# UPCB.net
KiCad netlist of a schematic drawn in EAGLE
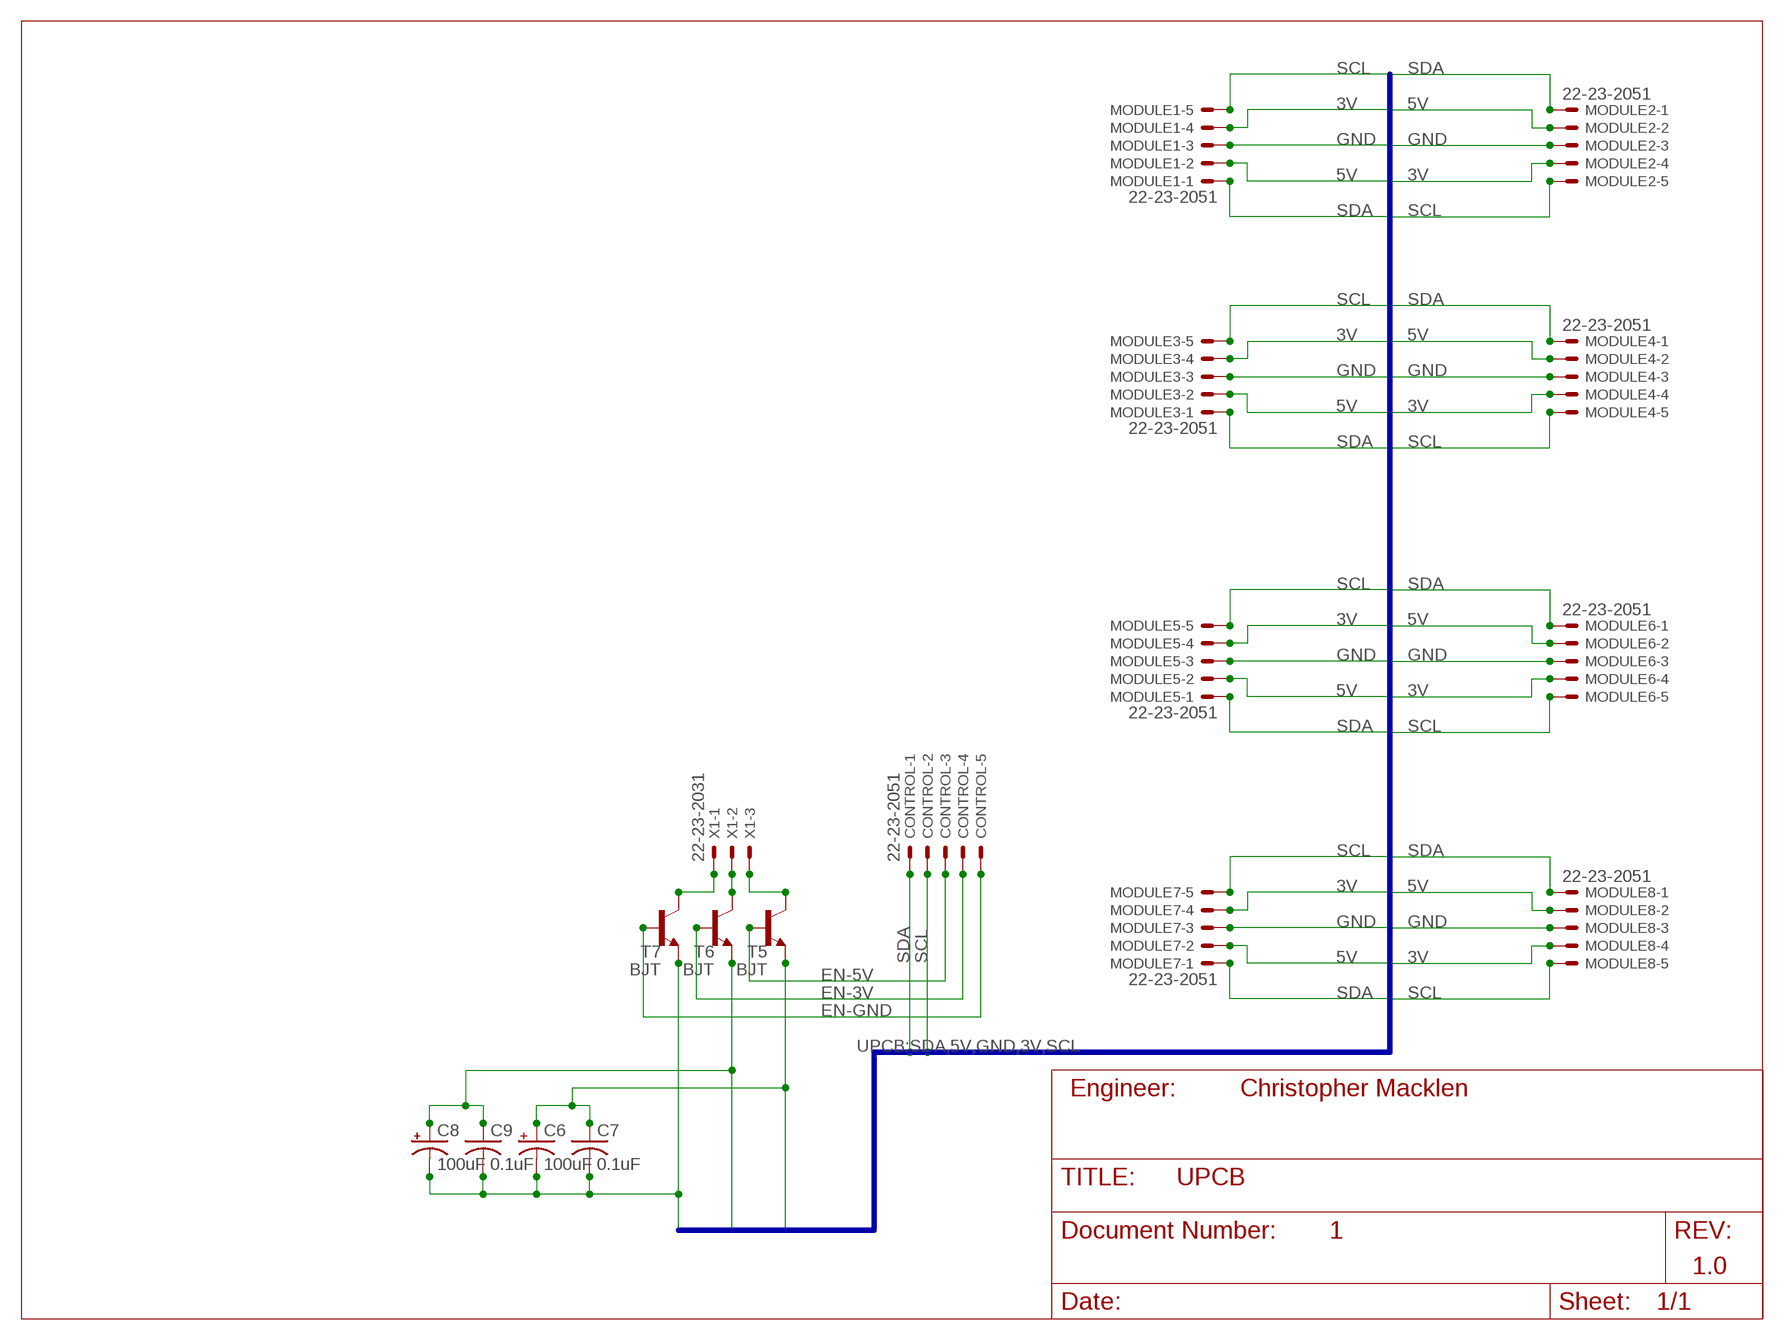
[diagram p0: schematic, sheet 1]

(export (version "E")
  (design (tool "Eeschema 10.0.6"))
  (components
    (comp (ref "C6")
      (value "100uF")
      (footprint "eagle-import:E2-5")
      (libsource (lib "eagle-import") (part "CPOL-USE2-5"))
    )
    (comp (ref "C7")
      (value "0.1uF")
      (footprint "eagle-import:C025-024X044")
      (libsource (lib "eagle-import") (part "C-US025-024X044"))
    )
    (comp (ref "C8")
      (value "100uF")
      (footprint "eagle-import:E2-5")
      (libsource (lib "eagle-import") (part "CPOL-USE2-5"))
    )
    (comp (ref "C9")
      (value "0.1uF")
      (footprint "eagle-import:C025-024X044")
      (libsource (lib "eagle-import") (part "C-US025-024X044"))
    )
    (comp (ref "CONTROL")
      (value "22-23-2051")
      (footprint "eagle-import:22-23-2051")
      (fields (field (name "MF") "MOLEX"))
      (libsource (lib "eagle-import") (part "22-23-2051"))
    )
    (comp (ref "MODULE1")
      (value "22-23-2051")
      (footprint "eagle-import:22-23-2051")
      (fields (field (name "MF") "MOLEX"))
      (libsource (lib "eagle-import") (part "22-23-2051"))
    )
    (comp (ref "MODULE2")
      (value "22-23-2051")
      (footprint "eagle-import:22-23-2051")
      (fields (field (name "MF") "MOLEX"))
      (libsource (lib "eagle-import") (part "22-23-2051"))
    )
    (comp (ref "MODULE3")
      (value "22-23-2051")
      (footprint "eagle-import:22-23-2051")
      (fields (field (name "MF") "MOLEX"))
      (libsource (lib "eagle-import") (part "22-23-2051"))
    )
    (comp (ref "MODULE4")
      (value "22-23-2051")
      (footprint "eagle-import:22-23-2051")
      (fields (field (name "MF") "MOLEX"))
      (libsource (lib "eagle-import") (part "22-23-2051"))
    )
    (comp (ref "MODULE5")
      (value "22-23-2051")
      (footprint "eagle-import:22-23-2051")
      (fields (field (name "MF") "MOLEX"))
      (libsource (lib "eagle-import") (part "22-23-2051"))
    )
    (comp (ref "MODULE6")
      (value "22-23-2051")
      (footprint "eagle-import:22-23-2051")
      (fields (field (name "MF") "MOLEX"))
      (libsource (lib "eagle-import") (part "22-23-2051"))
    )
    (comp (ref "MODULE7")
      (value "22-23-2051")
      (footprint "eagle-import:22-23-2051")
      (fields (field (name "MF") "MOLEX"))
      (libsource (lib "eagle-import") (part "22-23-2051"))
    )
    (comp (ref "MODULE8")
      (value "22-23-2051")
      (footprint "eagle-import:22-23-2051")
      (fields (field (name "MF") "MOLEX"))
      (libsource (lib "eagle-import") (part "22-23-2051"))
    )
    (comp (ref "T5")
      (value "BJT")
      (footprint "eagle-import:TO92-E1")
      (libsource (lib "eagle-import") (part "-NPN-TO92-E1"))
    )
    (comp (ref "T6")
      (value "BJT")
      (footprint "eagle-import:TO92-E1")
      (libsource (lib "eagle-import") (part "-NPN-TO92-E1"))
    )
    (comp (ref "T7")
      (value "BJT")
      (footprint "eagle-import:TO92-E1")
      (libsource (lib "eagle-import") (part "-NPN-TO92-E1"))
    )
    (comp (ref "X1")
      (value "22-23-2031")
      (footprint "eagle-import:22-23-2031")
      (fields (field (name "MF") "MOLEX"))
      (libsource (lib "eagle-import") (part "22-23-2031"))
    )
  )
  (nets
    (net (code "2") (name "/3V") (class "Default")
      (node (ref "C8") (pin "+") (pinfunction "+_+") (pintype "passive"))
      (node (ref "C9") (pin "1") (pinfunction "1_1") (pintype "passive"))
      (node (ref "MODULE1") (pin "4") (pinfunction "S_4") (pintype "passive"))
      (node (ref "MODULE2") (pin "4") (pinfunction "S_4") (pintype "passive"))
      (node (ref "MODULE3") (pin "4") (pinfunction "S_4") (pintype "passive"))
      (node (ref "MODULE4") (pin "4") (pinfunction "S_4") (pintype "passive"))
      (node (ref "MODULE5") (pin "4") (pinfunction "S_4") (pintype "passive"))
      (node (ref "MODULE6") (pin "4") (pinfunction "S_4") (pintype "passive"))
      (node (ref "MODULE7") (pin "4") (pinfunction "S_4") (pintype "passive"))
      (node (ref "MODULE8") (pin "4") (pinfunction "S_4") (pintype "passive"))
      (node (ref "T6") (pin "3") (pinfunction "E_3") (pintype "passive"))
    )
    (net (code "3") (name "/5V") (class "Default")
      (node (ref "C6") (pin "+") (pinfunction "+_+") (pintype "passive"))
      (node (ref "C7") (pin "1") (pinfunction "1_1") (pintype "passive"))
      (node (ref "MODULE1") (pin "2") (pinfunction "S_2") (pintype "passive"))
      (node (ref "MODULE2") (pin "2") (pinfunction "S_2") (pintype "passive"))
      (node (ref "MODULE3") (pin "2") (pinfunction "S_2") (pintype "passive"))
      (node (ref "MODULE4") (pin "2") (pinfunction "S_2") (pintype "passive"))
      (node (ref "MODULE5") (pin "2") (pinfunction "S_2") (pintype "passive"))
      (node (ref "MODULE6") (pin "2") (pinfunction "S_2") (pintype "passive"))
      (node (ref "MODULE7") (pin "2") (pinfunction "S_2") (pintype "passive"))
      (node (ref "MODULE8") (pin "2") (pinfunction "S_2") (pintype "passive"))
      (node (ref "T5") (pin "3") (pinfunction "E_3") (pintype "passive"))
    )
    (net (code "4") (name "/EN-3V") (class "Default")
      (node (ref "CONTROL") (pin "4") (pinfunction "S_4") (pintype "passive"))
      (node (ref "T6") (pin "2") (pinfunction "B_2") (pintype "passive"))
    )
    (net (code "5") (name "/EN-5V") (class "Default")
      (node (ref "CONTROL") (pin "3") (pinfunction "S_3") (pintype "passive"))
      (node (ref "T5") (pin "2") (pinfunction "B_2") (pintype "passive"))
    )
    (net (code "6") (name "/EN-GND") (class "Default")
      (node (ref "CONTROL") (pin "5") (pinfunction "S_5") (pintype "passive"))
      (node (ref "T7") (pin "2") (pinfunction "B_2") (pintype "passive"))
    )
    (net (code "7") (name "/GND") (class "Default")
      (node (ref "C6") (pin "-") (pinfunction "-_-") (pintype "passive"))
      (node (ref "C7") (pin "2") (pinfunction "2_2") (pintype "passive"))
      (node (ref "C8") (pin "-") (pinfunction "-_-") (pintype "passive"))
      (node (ref "C9") (pin "2") (pinfunction "2_2") (pintype "passive"))
      (node (ref "MODULE1") (pin "3") (pinfunction "S_3") (pintype "passive"))
      (node (ref "MODULE2") (pin "3") (pinfunction "S_3") (pintype "passive"))
      (node (ref "MODULE3") (pin "3") (pinfunction "S_3") (pintype "passive"))
      (node (ref "MODULE4") (pin "3") (pinfunction "S_3") (pintype "passive"))
      (node (ref "MODULE5") (pin "3") (pinfunction "S_3") (pintype "passive"))
      (node (ref "MODULE6") (pin "3") (pinfunction "S_3") (pintype "passive"))
      (node (ref "MODULE7") (pin "3") (pinfunction "S_3") (pintype "passive"))
      (node (ref "MODULE8") (pin "3") (pinfunction "S_3") (pintype "passive"))
      (node (ref "T7") (pin "3") (pinfunction "E_3") (pintype "passive"))
    )
    (net (code "8") (name "/SCL") (class "Default")
      (node (ref "CONTROL") (pin "2") (pinfunction "S_2") (pintype "passive"))
      (node (ref "MODULE1") (pin "5") (pinfunction "S_5") (pintype "passive"))
      (node (ref "MODULE2") (pin "5") (pinfunction "S_5") (pintype "passive"))
      (node (ref "MODULE3") (pin "5") (pinfunction "S_5") (pintype "passive"))
      (node (ref "MODULE4") (pin "5") (pinfunction "S_5") (pintype "passive"))
      (node (ref "MODULE5") (pin "5") (pinfunction "S_5") (pintype "passive"))
      (node (ref "MODULE6") (pin "5") (pinfunction "S_5") (pintype "passive"))
      (node (ref "MODULE7") (pin "5") (pinfunction "S_5") (pintype "passive"))
      (node (ref "MODULE8") (pin "5") (pinfunction "S_5") (pintype "passive"))
    )
    (net (code "9") (name "/SDA") (class "Default")
      (node (ref "CONTROL") (pin "1") (pinfunction "S_1") (pintype "passive"))
      (node (ref "MODULE1") (pin "1") (pinfunction "S_1") (pintype "passive"))
      (node (ref "MODULE2") (pin "1") (pinfunction "S_1") (pintype "passive"))
      (node (ref "MODULE3") (pin "1") (pinfunction "S_1") (pintype "passive"))
      (node (ref "MODULE4") (pin "1") (pinfunction "S_1") (pintype "passive"))
      (node (ref "MODULE5") (pin "1") (pinfunction "S_1") (pintype "passive"))
      (node (ref "MODULE6") (pin "1") (pinfunction "S_1") (pintype "passive"))
      (node (ref "MODULE7") (pin "1") (pinfunction "S_1") (pintype "passive"))
      (node (ref "MODULE8") (pin "1") (pinfunction "S_1") (pintype "passive"))
    )
    (net (code "11") (name "Net-(T5-C)") (class "Default")
      (node (ref "T5") (pin "1") (pinfunction "C_1") (pintype "passive"))
      (node (ref "X1") (pin "3") (pinfunction "S_3") (pintype "passive"))
    )
    (net (code "12") (name "Net-(T6-C)") (class "Default")
      (node (ref "T6") (pin "1") (pinfunction "C_1") (pintype "passive"))
      (node (ref "X1") (pin "2") (pinfunction "S_2") (pintype "passive"))
    )
    (net (code "13") (name "Net-(T7-C)") (class "Default")
      (node (ref "T7") (pin "1") (pinfunction "C_1") (pintype "passive"))
      (node (ref "X1") (pin "1") (pinfunction "S_1") (pintype "passive"))
    )
  )
)
